# ESPAlarm.net
KiCad netlist of a schematic drawn in EAGLE
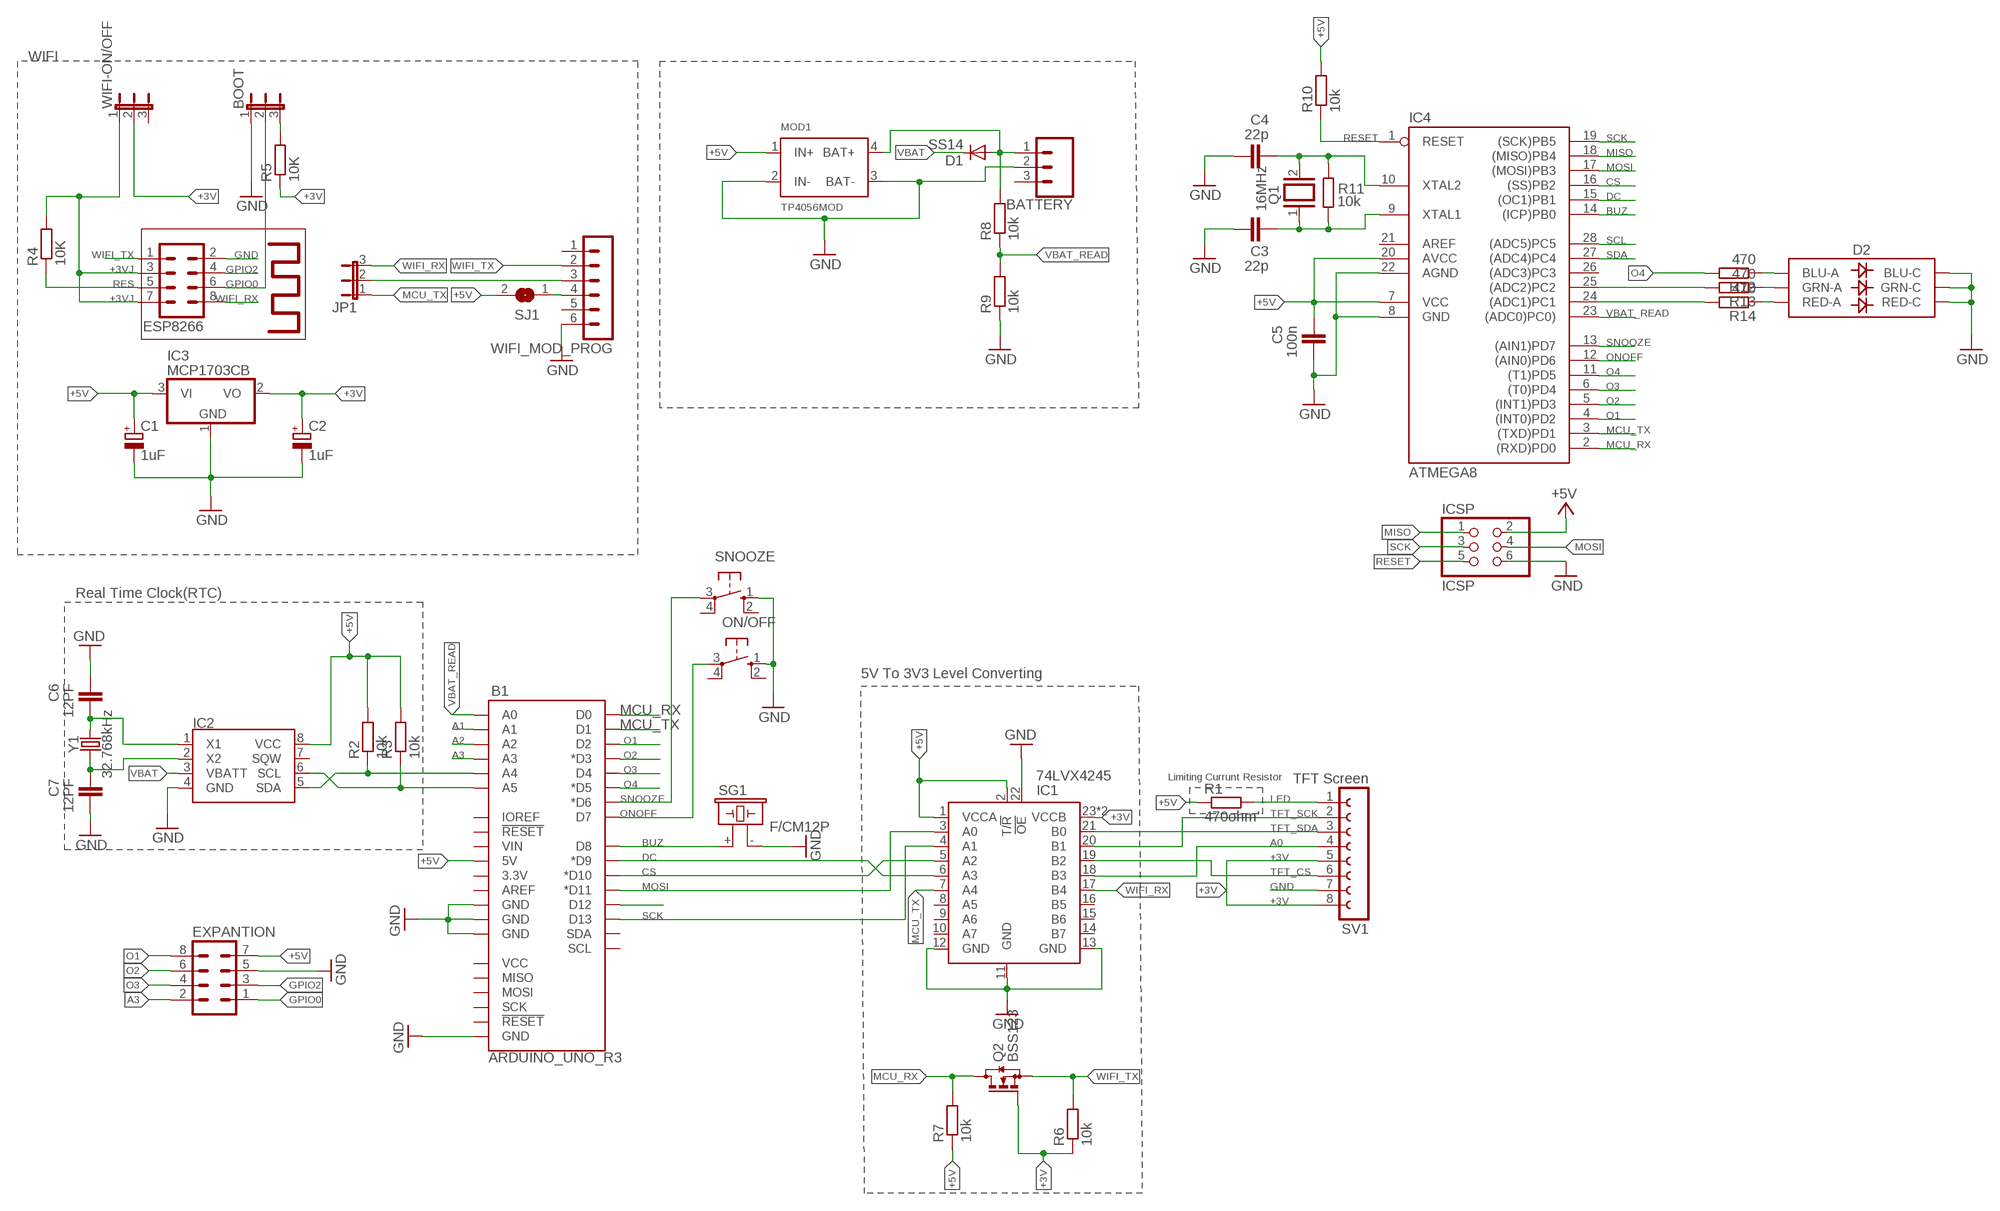
[diagram p0: schematic, sheet 1]

(export (version "E")
  (design (tool "Eeschema 10.0.6"))
  (components
    (comp (ref "B1")
      (value "ARDUINO_UNO_R3")
      (footprint "eagle-import:ARDUINO_R3")
      (libsource (lib "eagle-import") (part "ARDUINO_UNO_R3"))
    )
    (comp (ref "BATTERY")
      (value "CONN_03JST-PTH-VERT")
      (footprint "eagle-import:JST-3-PTH-VERT")
      (libsource (lib "eagle-import") (part "CONN_03JST-PTH-VERT"))
    )
    (comp (ref "BOOT")
      (value "JP2E")
      (footprint "eagle-import:JP2")
      (libsource (lib "eagle-import") (part "JP2E"))
    )
    (comp (ref "C1")
      (value "1uF")
      (footprint "eagle-import:E2,5-7")
      (libsource (lib "eagle-import") (part "CPOL-EUE2.5-7"))
    )
    (comp (ref "C2")
      (value "1uF")
      (footprint "eagle-import:E2,5-7")
      (libsource (lib "eagle-import") (part "CPOL-EUE2.5-7"))
    )
    (comp (ref "C3")
      (value "22p")
      (footprint "eagle-import:C0805")
      (libsource (lib "eagle-import") (part "C-EUC0805"))
    )
    (comp (ref "C4")
      (value "22p")
      (footprint "eagle-import:C0805")
      (libsource (lib "eagle-import") (part "C-EUC0805"))
    )
    (comp (ref "C5")
      (value "100n")
      (footprint "eagle-import:C0805")
      (libsource (lib "eagle-import") (part "C-EUC0805"))
    )
    (comp (ref "C6")
      (value "12PF")
      (footprint "eagle-import:C0805")
      (libsource (lib "eagle-import") (part "C-EUC0805"))
    )
    (comp (ref "C7")
      (value "12PF")
      (footprint "eagle-import:C0805")
      (libsource (lib "eagle-import") (part "C-EUC0805"))
    )
    (comp (ref "D1")
      (value "SS14")
      (footprint "eagle-import:DO214AC")
      (libsource (lib "eagle-import") (part "DIODE-DO214AC"))
    )
    (comp (ref "D2")
      (value "LED-RGBNO_IC")
      (footprint "eagle-import:LED-TRICOLOR-5050")
      (libsource (lib "eagle-import") (part "LED-RGBNO_IC"))
    )
    (comp (ref "ESP8266")
      (value "MA04-2")
      (footprint "eagle-import:MA04-2")
      (libsource (lib "eagle-import") (part "MA04-2"))
    )
    (comp (ref "EXPANTION")
      (value "MA04-2")
      (footprint "eagle-import:MA04-2")
      (libsource (lib "eagle-import") (part "MA04-2"))
    )
    (comp (ref "IC1")
      (value "74LVX4245")
      (footprint "eagle-import:TSSOP-24")
      (libsource (lib "eagle-import") (part "74LVX4245"))
    )
    (comp (ref "IC2")
      (value "DS1307")
      (footprint "eagle-import:DIP-08")
      (libsource (lib "eagle-import") (part "DS1307"))
    )
    (comp (ref "IC3")
      (value "MCP1703CB")
      (footprint "eagle-import:SOT23")
      (libsource (lib "eagle-import") (part "MCP1703CB"))
    )
    (comp (ref "IC4")
      (value "ATMEGA8")
      (footprint "eagle-import:DIL28-3")
      (libsource (lib "eagle-import") (part "AT90S4433P"))
    )
    (comp (ref "ICSP")
      (value "ICSP")
      (footprint "eagle-import:2X03")
      (libsource (lib "eagle-import") (part "PINHD-2X3"))
    )
    (comp (ref "JP1")
      (value "JP2E")
      (footprint "eagle-import:JP2")
      (libsource (lib "eagle-import") (part "JP2E"))
    )
    (comp (ref "MOD1")
      (value "TP4056MOD")
      (footprint "eagle-import:TP4056BRD")
      (libsource (lib "eagle-import") (part "TP4056MOD"))
    )
    (comp (ref "ON/OFF")
      (value "10-XX")
      (footprint "eagle-import:B3F-10XX")
      (fields (field (name "MPN") "B3F-1000"))
      (libsource (lib "eagle-import") (part "10-XX"))
    )
    (comp (ref "Q1")
      (value "16MHz")
      (footprint "eagle-import:SMARTPRJ_QS")
      (libsource (lib "eagle-import") (part "SMARTPRJ_XTAL/S"))
    )
    (comp (ref "Q2")
      (value "BSS123")
      (footprint "eagle-import:SOT23")
      (libsource (lib "eagle-import") (part "BSS123"))
    )
    (comp (ref "R1")
      (value "470ohm'")
      (footprint "eagle-import:M1206")
      (libsource (lib "eagle-import") (part "R-EU_M1206"))
    )
    (comp (ref "R2")
      (value "10k")
      (footprint "eagle-import:M1206")
      (libsource (lib "eagle-import") (part "R-EU_M1206"))
    )
    (comp (ref "R3")
      (value "10k")
      (footprint "eagle-import:M1206")
      (libsource (lib "eagle-import") (part "R-EU_M1206"))
    )
    (comp (ref "R4")
      (value "10K")
      (footprint "eagle-import:M1206")
      (libsource (lib "eagle-import") (part "R-EU_M1206"))
    )
    (comp (ref "R5")
      (value "10K")
      (footprint "eagle-import:M1206")
      (libsource (lib "eagle-import") (part "R-EU_M1206"))
    )
    (comp (ref "R6")
      (value "10k")
      (footprint "eagle-import:M1206")
      (libsource (lib "eagle-import") (part "R-EU_M1206"))
    )
    (comp (ref "R7")
      (value "10k")
      (footprint "eagle-import:M1206")
      (libsource (lib "eagle-import") (part "R-EU_M1206"))
    )
    (comp (ref "R8")
      (value "10k")
      (footprint "eagle-import:M1206")
      (libsource (lib "eagle-import") (part "R-EU_M1206"))
    )
    (comp (ref "R9")
      (value "10k")
      (footprint "eagle-import:M1206")
      (libsource (lib "eagle-import") (part "R-EU_M1206"))
    )
    (comp (ref "R10")
      (value "10k")
      (footprint "eagle-import:M1206")
      (libsource (lib "eagle-import") (part "R-EU_M1206"))
    )
    (comp (ref "R11")
      (value "10k")
      (footprint "eagle-import:M1206")
      (libsource (lib "eagle-import") (part "R-EU_M1206"))
    )
    (comp (ref "R12")
      (value "470")
      (footprint "eagle-import:M1206")
      (libsource (lib "eagle-import") (part "R-EU_M1206"))
    )
    (comp (ref "R13")
      (value "470")
      (footprint "eagle-import:M1206")
      (libsource (lib "eagle-import") (part "R-EU_M1206"))
    )
    (comp (ref "R14")
      (value "470")
      (footprint "eagle-import:M1206")
      (libsource (lib "eagle-import") (part "R-EU_M1206"))
    )
    (comp (ref "SG1")
      (value "F/CM12P")
      (footprint "eagle-import:F_CM12P")
      (libsource (lib "eagle-import") (part "F/CM12P"))
    )
    (comp (ref "SJ1") (value "SJ") (footprint "eagle-import:SJ") (libsource (lib "eagle-import") (part "SJ")))
    (comp (ref "SNOOZE")
      (value "10-XX")
      (footprint "eagle-import:B3F-10XX")
      (fields (field (name "MPN") "B3F-1000"))
      (libsource (lib "eagle-import") (part "10-XX"))
    )
    (comp (ref "SV1")
      (value "TFT Screen")
      (footprint "eagle-import:FE08")
      (libsource (lib "eagle-import") (part "FE08-1"))
    )
    (comp (ref "WIFI-ON/OFF")
      (value "JP2E")
      (footprint "eagle-import:JP2")
      (libsource (lib "eagle-import") (part "JP2E"))
    )
    (comp (ref "WIFI_MOD_PROG")
      (value "MA06-1")
      (footprint "eagle-import:MA06-1")
      (libsource (lib "eagle-import") (part "MA06-1"))
    )
    (comp (ref "Y1")
      (value "32.768kHz")
      (footprint "eagle-import:CRYSTAL-PTH-2X6-CYL")
      (libsource (lib "eagle-import") (part "CRYSTAL-32.768KHZPTH-2X6"))
    )
  )
  (nets
    (net (code "1") (name "+3V") (class "Default")
      (node (ref "C2") (pin "+") (pinfunction "+_+") (pintype "passive"))
      (node (ref "IC1") (pin "23") (pinfunction "VCCB_23") (pintype "power_in"))
      (node (ref "IC1") (pin "24") (pinfunction "VCCB_24") (pintype "power_in"))
      (node (ref "IC3") (pin "2") (pinfunction "VO_2") (pintype "passive"))
      (node (ref "Q2") (pin "1") (pinfunction "G_1") (pintype "passive"))
      (node (ref "R5") (pin "1") (pinfunction "1_1") (pintype "passive"))
      (node (ref "R6") (pin "1") (pinfunction "1_1") (pintype "passive"))
      (node (ref "SV1") (pin "5") (pinfunction "5_5") (pintype "passive"))
      (node (ref "SV1") (pin "8") (pinfunction "8_8") (pintype "passive"))
      (node (ref "WIFI-ON/OFF") (pin "2") (pinfunction "2_2") (pintype "passive"))
    )
    (net (code "2") (name "+5V") (class "Default")
      (node (ref "B1") (pin "5V") (pinfunction "5V_5V") (pintype "bidirectional"))
      (node (ref "C1") (pin "+") (pinfunction "+_+") (pintype "passive"))
      (node (ref "C5") (pin "2") (pinfunction "2_2") (pintype "passive"))
      (node (ref "EXPANTION") (pin "7") (pinfunction "7_7") (pintype "passive"))
      (node (ref "IC1") (pin "1") (pinfunction "VCCA_1") (pintype "power_in"))
      (node (ref "IC1") (pin "2") (pinfunction "T/~{R}_2") (pintype "open_collector"))
      (node (ref "IC2") (pin "8") (pinfunction "VCC_8") (pintype "bidirectional"))
      (node (ref "IC3") (pin "3") (pinfunction "VI_3") (pintype "input"))
      (node (ref "IC4") (pin "20") (pinfunction "AVCC_20") (pintype "power_in"))
      (node (ref "IC4") (pin "7") (pinfunction "VCC_7") (pintype "power_in"))
      (node (ref "ICSP") (pin "2") (pinfunction "2_2") (pintype "passive"))
      (node (ref "MOD1") (pin "1") (pinfunction "IN+_1") (pintype "bidirectional"))
      (node (ref "R1") (pin "1") (pinfunction "1_1") (pintype "passive"))
      (node (ref "R10") (pin "2") (pinfunction "2_2") (pintype "passive"))
      (node (ref "R2") (pin "2") (pinfunction "2_2") (pintype "passive"))
      (node (ref "R3") (pin "2") (pinfunction "2_2") (pintype "passive"))
      (node (ref "R7") (pin "1") (pinfunction "1_1") (pintype "passive"))
      (node (ref "SJ1") (pin "2") (pinfunction "2_2") (pintype "passive"))
    )
    (net (code "3") (name "/+3VJ") (class "Default")
      (node (ref "ESP8266") (pin "3") (pinfunction "3_3") (pintype "passive"))
      (node (ref "ESP8266") (pin "7") (pinfunction "7_7") (pintype "passive"))
      (node (ref "R4") (pin "2") (pinfunction "2_2") (pintype "passive"))
      (node (ref "WIFI-ON/OFF") (pin "1") (pinfunction "1_1") (pintype "passive"))
    )
    (net (code "4") (name "/A0") (class "Default")
      (node (ref "IC1") (pin "18") (pinfunction "B3_18") (pintype "bidirectional"))
      (node (ref "SV1") (pin "4") (pinfunction "4_4") (pintype "passive"))
    )
    (net (code "5") (name "/A1") (class "Default")
      (node (ref "B1") (pin "A1") (pinfunction "A1_A1") (pintype "bidirectional"))
      (node (ref "IC4") (pin "24") (pinfunction "(ADC1)PC1_24") (pintype "bidirectional"))
      (node (ref "R14") (pin "2") (pinfunction "2_2") (pintype "passive"))
    )
    (net (code "6") (name "/A2") (class "Default")
      (node (ref "B1") (pin "A2") (pinfunction "A2_A2") (pintype "bidirectional"))
      (node (ref "IC4") (pin "25") (pinfunction "(ADC2)PC2_25") (pintype "bidirectional"))
      (node (ref "R13") (pin "2") (pinfunction "2_2") (pintype "passive"))
    )
    (net (code "7") (name "/AREF") (class "Default")
      (node (ref "IC4") (pin "21") (pinfunction "AREF_21") (pintype "power_in"))
    )
    (net (code "8") (name "/BUZ") (class "Default")
      (node (ref "B1") (pin "D8") (pinfunction "D8_D8") (pintype "bidirectional"))
      (node (ref "IC4") (pin "14") (pinfunction "(ICP)PB0_14") (pintype "bidirectional"))
      (node (ref "SG1") (pin "+") (pinfunction "1_+") (pintype "passive"))
    )
    (net (code "9") (name "/CS") (class "Default")
      (node (ref "B1") (pin "D10") (pinfunction "*D10_D10") (pintype "bidirectional"))
      (node (ref "IC1") (pin "5") (pinfunction "A2_5") (pintype "bidirectional"))
      (node (ref "IC4") (pin "16") (pinfunction "(SS)PB2_16") (pintype "bidirectional"))
    )
    (net (code "10") (name "/DC") (class "Default")
      (node (ref "B1") (pin "D9") (pinfunction "*D9_D9") (pintype "bidirectional"))
      (node (ref "IC1") (pin "6") (pinfunction "A3_6") (pintype "bidirectional"))
      (node (ref "IC4") (pin "15") (pinfunction "(OC1)PB1_15") (pintype "bidirectional"))
    )
    (net (code "11") (name "/LED") (class "Default")
      (node (ref "R1") (pin "2") (pinfunction "2_2") (pintype "passive"))
      (node (ref "SV1") (pin "1") (pinfunction "1_1") (pintype "passive"))
    )
    (net (code "12") (name "/ONOFF") (class "Default")
      (node (ref "B1") (pin "D7") (pinfunction "D7_D7") (pintype "bidirectional"))
      (node (ref "IC4") (pin "12") (pinfunction "(AIN0)PD6_12") (pintype "bidirectional"))
      (node (ref "ON/OFF") (pin "3") (pinfunction "P_3") (pintype "passive"))
    )
    (net (code "13") (name "/RES") (class "Default")
      (node (ref "ESP8266") (pin "5") (pinfunction "5_5") (pintype "passive"))
      (node (ref "R4") (pin "1") (pinfunction "1_1") (pintype "passive"))
    )
    (net (code "14") (name "/SCL") (class "Default")
      (node (ref "B1") (pin "A5") (pinfunction "A5_A5") (pintype "bidirectional"))
      (node (ref "IC2") (pin "6") (pinfunction "SCL_6") (pintype "bidirectional"))
      (node (ref "IC4") (pin "28") (pinfunction "(ADC5)PC5_28") (pintype "bidirectional"))
      (node (ref "R3") (pin "1") (pinfunction "1_1") (pintype "passive"))
    )
    (net (code "15") (name "/SDA") (class "Default")
      (node (ref "B1") (pin "A4") (pinfunction "A4_A4") (pintype "bidirectional"))
      (node (ref "IC2") (pin "5") (pinfunction "SDA_5") (pintype "bidirectional"))
      (node (ref "IC4") (pin "27") (pinfunction "(ADC4)PC4_27") (pintype "bidirectional"))
      (node (ref "R2") (pin "1") (pinfunction "1_1") (pintype "passive"))
    )
    (net (code "16") (name "/SNOOZE") (class "Default")
      (node (ref "B1") (pin "D6") (pinfunction "*D6_D6") (pintype "bidirectional"))
      (node (ref "IC4") (pin "13") (pinfunction "(AIN1)PD7_13") (pintype "bidirectional"))
      (node (ref "SNOOZE") (pin "3") (pinfunction "P_3") (pintype "passive"))
    )
    (net (code "17") (name "/TFT_CS") (class "Default")
      (node (ref "IC1") (pin "19") (pinfunction "B2_19") (pintype "bidirectional"))
      (node (ref "SV1") (pin "6") (pinfunction "6_6") (pintype "passive"))
    )
    (net (code "18") (name "/TFT_SCK") (class "Default")
      (node (ref "IC1") (pin "20") (pinfunction "B1_20") (pintype "bidirectional"))
      (node (ref "SV1") (pin "2") (pinfunction "2_2") (pintype "passive"))
    )
    (net (code "19") (name "/TFT_SDA") (class "Default")
      (node (ref "IC1") (pin "21") (pinfunction "B0_21") (pintype "bidirectional"))
      (node (ref "SV1") (pin "3") (pinfunction "3_3") (pintype "passive"))
    )
    (net (code "20") (name "A3") (class "Default")
      (node (ref "B1") (pin "A3") (pinfunction "A3_A3") (pintype "bidirectional"))
      (node (ref "EXPANTION") (pin "2") (pinfunction "2_2") (pintype "passive"))
    )
    (net (code "21") (name "GND") (class "Default")
      (node (ref "B1") (pin "GND@1") (pinfunction "GND_GND@1") (pintype "bidirectional"))
      (node (ref "B1") (pin "GND@2") (pinfunction "GND_GND@2") (pintype "bidirectional"))
      (node (ref "B1") (pin "GND@3") (pinfunction "GND_GND@3") (pintype "bidirectional"))
      (node (ref "B1") (pin "GND@4") (pinfunction "GND_GND@4") (pintype "bidirectional"))
      (node (ref "BATTERY") (pin "2") (pinfunction "2_2") (pintype "passive"))
      (node (ref "BOOT") (pin "1") (pinfunction "1_1") (pintype "passive"))
      (node (ref "C1") (pin "-") (pinfunction "-_-") (pintype "passive"))
      (node (ref "C2") (pin "-") (pinfunction "-_-") (pintype "passive"))
      (node (ref "C3") (pin "1") (pinfunction "1_1") (pintype "passive"))
      (node (ref "C4") (pin "1") (pinfunction "1_1") (pintype "passive"))
      (node (ref "C5") (pin "1") (pinfunction "1_1") (pintype "passive"))
      (node (ref "C6") (pin "2") (pinfunction "2_2") (pintype "passive"))
      (node (ref "C7") (pin "1") (pinfunction "1_1") (pintype "passive"))
      (node (ref "D2") (pin "4") (pinfunction "BLU-C_4") (pintype "bidirectional"))
      (node (ref "D2") (pin "5") (pinfunction "RED-C_5") (pintype "bidirectional"))
      (node (ref "D2") (pin "6") (pinfunction "GRN-C_6") (pintype "bidirectional"))
      (node (ref "ESP8266") (pin "2") (pinfunction "2_2") (pintype "passive"))
      (node (ref "EXPANTION") (pin "5") (pinfunction "5_5") (pintype "passive"))
      (node (ref "IC1") (pin "11") (pinfunction "GND_11") (pintype "power_in"))
      (node (ref "IC1") (pin "12") (pinfunction "GND_12") (pintype "power_in"))
      (node (ref "IC1") (pin "13") (pinfunction "GND_13") (pintype "power_in"))
      (node (ref "IC1") (pin "22") (pinfunction "~{OE}_22") (pintype "open_collector"))
      (node (ref "IC2") (pin "4") (pinfunction "GND_4") (pintype "bidirectional"))
      (node (ref "IC3") (pin "1") (pinfunction "GND_1") (pintype "passive"))
      (node (ref "IC4") (pin "22") (pinfunction "AGND_22") (pintype "power_in"))
      (node (ref "IC4") (pin "8") (pinfunction "GND_8") (pintype "power_in"))
      (node (ref "ICSP") (pin "6") (pinfunction "6_6") (pintype "passive"))
      (node (ref "MOD1") (pin "2") (pinfunction "IN-_2") (pintype "bidirectional"))
      (node (ref "MOD1") (pin "3") (pinfunction "BAT-_3") (pintype "bidirectional"))
      (node (ref "ON/OFF") (pin "1") (pinfunction "S_1") (pintype "passive"))
      (node (ref "R9") (pin "1") (pinfunction "1_1") (pintype "passive"))
      (node (ref "SG1") (pin "-") (pinfunction "2_-") (pintype "passive"))
      (node (ref "SNOOZE") (pin "1") (pinfunction "S_1") (pintype "passive"))
      (node (ref "SV1") (pin "7") (pinfunction "7_7") (pintype "passive"))
      (node (ref "WIFI_MOD_PROG") (pin "6") (pinfunction "6_6") (pintype "passive"))
    )
    (net (code "22") (name "GPIO0") (class "Default")
      (node (ref "BOOT") (pin "2") (pinfunction "2_2") (pintype "passive"))
      (node (ref "ESP8266") (pin "6") (pinfunction "6_6") (pintype "passive"))
      (node (ref "EXPANTION") (pin "1") (pinfunction "1_1") (pintype "passive"))
    )
    (net (code "23") (name "GPIO2") (class "Default")
      (node (ref "ESP8266") (pin "4") (pinfunction "4_4") (pintype "passive"))
      (node (ref "EXPANTION") (pin "3") (pinfunction "3_3") (pintype "passive"))
    )
    (net (code "24") (name "MCU_RX") (class "Default")
      (node (ref "B1") (pin "D0") (pinfunction "D0_D0") (pintype "bidirectional"))
      (node (ref "IC4") (pin "2") (pinfunction "(RXD)PD0_2") (pintype "bidirectional"))
      (node (ref "Q2") (pin "3") (pinfunction "D_3") (pintype "passive"))
      (node (ref "R7") (pin "2") (pinfunction "2_2") (pintype "passive"))
    )
    (net (code "25") (name "MCU_TX") (class "Default")
      (node (ref "B1") (pin "D1") (pinfunction "D1_D1") (pintype "bidirectional"))
      (node (ref "IC1") (pin "7") (pinfunction "A4_7") (pintype "bidirectional"))
      (node (ref "IC4") (pin "3") (pinfunction "(TXD)PD1_3") (pintype "bidirectional"))
      (node (ref "JP1") (pin "1") (pinfunction "1_1") (pintype "passive"))
    )
    (net (code "26") (name "MISO") (class "Default")
      (node (ref "IC4") (pin "18") (pinfunction "(MISO)PB4_18") (pintype "bidirectional"))
      (node (ref "ICSP") (pin "1") (pinfunction "1_1") (pintype "passive"))
    )
    (net (code "27") (name "MOSI") (class "Default")
      (node (ref "B1") (pin "D11") (pinfunction "*D11_D11") (pintype "bidirectional"))
      (node (ref "IC1") (pin "3") (pinfunction "A0_3") (pintype "bidirectional"))
      (node (ref "IC4") (pin "17") (pinfunction "(MOSI)PB3_17") (pintype "bidirectional"))
      (node (ref "ICSP") (pin "4") (pinfunction "4_4") (pintype "passive"))
    )
    (net (code "28") (name "Net-(BOOT-Pad3)") (class "Default")
      (node (ref "BOOT") (pin "3") (pinfunction "3_3") (pintype "passive"))
      (node (ref "R5") (pin "2") (pinfunction "2_2") (pintype "passive"))
    )
    (net (code "29") (name "Net-(D2-BLU-A)") (class "Default")
      (node (ref "D2") (pin "3") (pinfunction "BLU-A_3") (pintype "bidirectional"))
      (node (ref "R12") (pin "1") (pinfunction "1_1") (pintype "passive"))
    )
    (net (code "30") (name "Net-(D2-GRN-A)") (class "Default")
      (node (ref "D2") (pin "1") (pinfunction "GRN-A_1") (pintype "bidirectional"))
      (node (ref "R13") (pin "1") (pinfunction "1_1") (pintype "passive"))
    )
    (net (code "31") (name "Net-(D2-RED-A)") (class "Default")
      (node (ref "D2") (pin "2") (pinfunction "RED-A_2") (pintype "bidirectional"))
      (node (ref "R14") (pin "1") (pinfunction "1_1") (pintype "passive"))
    )
    (net (code "32") (name "Net-(IC2-X1)") (class "Default")
      (node (ref "C6") (pin "1") (pinfunction "1_1") (pintype "passive"))
      (node (ref "IC2") (pin "1") (pinfunction "X1_1") (pintype "bidirectional"))
      (node (ref "Y1") (pin "2") (pinfunction "2_2") (pintype "passive"))
    )
    (net (code "33") (name "Net-(IC2-X2)") (class "Default")
      (node (ref "C7") (pin "2") (pinfunction "2_2") (pintype "passive"))
      (node (ref "IC2") (pin "2") (pinfunction "X2_2") (pintype "bidirectional"))
      (node (ref "Y1") (pin "1") (pinfunction "1_1") (pintype "passive"))
    )
    (net (code "34") (name "Net-(IC4-XTAL1)") (class "Default")
      (node (ref "C3") (pin "2") (pinfunction "2_2") (pintype "passive"))
      (node (ref "IC4") (pin "9") (pinfunction "XTAL1_9") (pintype "bidirectional"))
      (node (ref "Q1") (pin "1") (pinfunction "1_1") (pintype "passive"))
      (node (ref "R11") (pin "1") (pinfunction "1_1") (pintype "passive"))
    )
    (net (code "35") (name "Net-(IC4-XTAL2)") (class "Default")
      (node (ref "C4") (pin "2") (pinfunction "2_2") (pintype "passive"))
      (node (ref "IC4") (pin "10") (pinfunction "XTAL2_10") (pintype "bidirectional"))
      (node (ref "Q1") (pin "2") (pinfunction "2_2") (pintype "passive"))
      (node (ref "R11") (pin "2") (pinfunction "2_2") (pintype "passive"))
    )
    (net (code "36") (name "Net-(JP1-Pad2)") (class "Default")
      (node (ref "JP1") (pin "2") (pinfunction "2_2") (pintype "passive"))
      (node (ref "WIFI_MOD_PROG") (pin "3") (pinfunction "3_3") (pintype "passive"))
    )
    (net (code "37") (name "Net-(MOD1-BAT+)") (class "Default")
      (node (ref "BATTERY") (pin "1") (pinfunction "1_1") (pintype "passive"))
      (node (ref "D1") (pin "A") (pinfunction "A_A") (pintype "passive"))
      (node (ref "MOD1") (pin "4") (pinfunction "BAT+_4") (pintype "bidirectional"))
      (node (ref "R8") (pin "2") (pinfunction "2_2") (pintype "passive"))
    )
    (net (code "38") (name "Net-(SJ1-Pad1)") (class "Default")
      (node (ref "SJ1") (pin "1") (pinfunction "1_1") (pintype "passive"))
      (node (ref "WIFI_MOD_PROG") (pin "4") (pinfunction "4_4") (pintype "passive"))
    )
    (net (code "39") (name "O1") (class "Default")
      (node (ref "B1") (pin "D2") (pinfunction "D2_D2") (pintype "bidirectional"))
      (node (ref "EXPANTION") (pin "8") (pinfunction "8_8") (pintype "passive"))
      (node (ref "IC4") (pin "4") (pinfunction "(INT0)PD2_4") (pintype "bidirectional"))
    )
    (net (code "40") (name "O2") (class "Default")
      (node (ref "B1") (pin "D3") (pinfunction "*D3_D3") (pintype "bidirectional"))
      (node (ref "EXPANTION") (pin "6") (pinfunction "6_6") (pintype "passive"))
      (node (ref "IC4") (pin "5") (pinfunction "(INT1)PD3_5") (pintype "bidirectional"))
    )
    (net (code "41") (name "O3") (class "Default")
      (node (ref "B1") (pin "D4") (pinfunction "D4_D4") (pintype "bidirectional"))
      (node (ref "EXPANTION") (pin "4") (pinfunction "4_4") (pintype "passive"))
      (node (ref "IC4") (pin "6") (pinfunction "(T0)PD4_6") (pintype "bidirectional"))
    )
    (net (code "42") (name "O4") (class "Default")
      (node (ref "B1") (pin "D5") (pinfunction "*D5_D5") (pintype "bidirectional"))
      (node (ref "IC4") (pin "11") (pinfunction "(T1)PD5_11") (pintype "bidirectional"))
      (node (ref "R12") (pin "2") (pinfunction "2_2") (pintype "passive"))
    )
    (net (code "43") (name "RESET") (class "Default")
      (node (ref "IC4") (pin "1") (pinfunction "RESET_1") (pintype "input"))
      (node (ref "ICSP") (pin "5") (pinfunction "5_5") (pintype "passive"))
      (node (ref "R10") (pin "1") (pinfunction "1_1") (pintype "passive"))
    )
    (net (code "44") (name "SCK") (class "Default")
      (node (ref "B1") (pin "D13") (pinfunction "D13_D13") (pintype "bidirectional"))
      (node (ref "IC1") (pin "4") (pinfunction "A1_4") (pintype "bidirectional"))
      (node (ref "IC4") (pin "19") (pinfunction "(SCK)PB5_19") (pintype "bidirectional"))
      (node (ref "ICSP") (pin "3") (pinfunction "3_3") (pintype "passive"))
    )
    (net (code "45") (name "VBAT") (class "Default")
      (node (ref "D1") (pin "C") (pinfunction "C_C") (pintype "passive"))
      (node (ref "IC2") (pin "3") (pinfunction "VBATT_3") (pintype "bidirectional"))
    )
    (net (code "46") (name "VBAT_READ") (class "Default")
      (node (ref "B1") (pin "A0") (pinfunction "A0_A0") (pintype "bidirectional"))
      (node (ref "IC4") (pin "23") (pinfunction "(ADC0)PC0)_23") (pintype "bidirectional"))
      (node (ref "R8") (pin "1") (pinfunction "1_1") (pintype "passive"))
      (node (ref "R9") (pin "2") (pinfunction "2_2") (pintype "passive"))
    )
    (net (code "47") (name "WIFI_RX") (class "Default")
      (node (ref "ESP8266") (pin "8") (pinfunction "8_8") (pintype "passive"))
      (node (ref "IC1") (pin "17") (pinfunction "B4_17") (pintype "bidirectional"))
      (node (ref "JP1") (pin "3") (pinfunction "3_3") (pintype "passive"))
    )
    (net (code "48") (name "WIFI_TX") (class "Default")
      (node (ref "ESP8266") (pin "1") (pinfunction "1_1") (pintype "passive"))
      (node (ref "Q2") (pin "2") (pinfunction "S_2") (pintype "passive"))
      (node (ref "R6") (pin "2") (pinfunction "2_2") (pintype "passive"))
      (node (ref "WIFI_MOD_PROG") (pin "2") (pinfunction "2_2") (pintype "passive"))
    )
    (net (code "49") (name "unconnected-(B1-Pad3.3V)") (class "Default")
      (node (ref "B1") (pin "3.3V") (pinfunction "3.3V_3.3V") (pintype "bidirectional"))
    )
    (net (code "50") (name "unconnected-(B1-PadAREF)") (class "Default")
      (node (ref "B1") (pin "AREF") (pinfunction "AREF_AREF") (pintype "bidirectional"))
    )
    (net (code "51") (name "unconnected-(B1-PadD12)") (class "Default")
      (node (ref "B1") (pin "D12") (pinfunction "D12_D12") (pintype "bidirectional"))
    )
    (net (code "52") (name "unconnected-(B1-PadIOREF)") (class "Default")
      (node (ref "B1") (pin "IOREF") (pinfunction "IOREF_IOREF") (pintype "bidirectional"))
    )
    (net (code "53") (name "unconnected-(B1-PadMISO)") (class "Default")
      (node (ref "B1") (pin "MISO") (pinfunction "MISO_MISO") (pintype "bidirectional"))
    )
    (net (code "54") (name "unconnected-(B1-PadMOSI)") (class "Default")
      (node (ref "B1") (pin "MOSI") (pinfunction "MOSI_MOSI") (pintype "bidirectional"))
    )
    (net (code "55") (name "unconnected-(B1-PadSCK)") (class "Default")
      (node (ref "B1") (pin "SCK") (pinfunction "SCK_SCK") (pintype "bidirectional"))
    )
    (net (code "56") (name "unconnected-(B1-PadSCL)") (class "Default")
      (node (ref "B1") (pin "SCL") (pinfunction "SCL_SCL") (pintype "bidirectional"))
    )
    (net (code "57") (name "unconnected-(B1-PadSDA)") (class "Default")
      (node (ref "B1") (pin "SDA") (pinfunction "SDA_SDA") (pintype "bidirectional"))
    )
    (net (code "58") (name "unconnected-(B1-PadVCC)") (class "Default")
      (node (ref "B1") (pin "VCC") (pinfunction "VCC_VCC") (pintype "bidirectional"))
    )
    (net (code "59") (name "unconnected-(B1-PadVIN)") (class "Default")
      (node (ref "B1") (pin "VIN") (pinfunction "VIN_VIN") (pintype "bidirectional"))
    )
    (net (code "60") (name "unconnected-(B1-~{RESET}-PadRESET@1)") (class "Default")
      (node (ref "B1") (pin "RESET@1") (pinfunction "~{RESET}_RESET@1") (pintype "bidirectional"))
    )
    (net (code "61") (name "unconnected-(B1-~{RESET}-PadRESET@2)") (class "Default")
      (node (ref "B1") (pin "RESET@2") (pinfunction "~{RESET}_RESET@2") (pintype "bidirectional"))
    )
    (net (code "62") (name "unconnected-(BATTERY-Pad3)") (class "Default")
      (node (ref "BATTERY") (pin "3") (pinfunction "3_3") (pintype "passive"))
    )
    (net (code "63") (name "unconnected-(IC1-A5-Pad8)") (class "Default")
      (node (ref "IC1") (pin "8") (pinfunction "A5_8") (pintype "bidirectional"))
    )
    (net (code "64") (name "unconnected-(IC1-A6-Pad9)") (class "Default")
      (node (ref "IC1") (pin "9") (pinfunction "A6_9") (pintype "bidirectional"))
    )
    (net (code "65") (name "unconnected-(IC1-A7-Pad10)") (class "Default")
      (node (ref "IC1") (pin "10") (pinfunction "A7_10") (pintype "bidirectional"))
    )
    (net (code "66") (name "unconnected-(IC1-B5-Pad16)") (class "Default")
      (node (ref "IC1") (pin "16") (pinfunction "B5_16") (pintype "bidirectional"))
    )
    (net (code "67") (name "unconnected-(IC1-B6-Pad15)") (class "Default")
      (node (ref "IC1") (pin "15") (pinfunction "B6_15") (pintype "bidirectional"))
    )
    (net (code "68") (name "unconnected-(IC1-B7-Pad14)") (class "Default")
      (node (ref "IC1") (pin "14") (pinfunction "B7_14") (pintype "bidirectional"))
    )
    (net (code "69") (name "unconnected-(IC2-SQW-Pad7)") (class "Default")
      (node (ref "IC2") (pin "7") (pinfunction "SQW_7") (pintype "bidirectional"))
    )
    (net (code "70") (name "unconnected-(IC4-(ADC3)PC3-Pad26)") (class "Default")
      (node (ref "IC4") (pin "26") (pinfunction "(ADC3)PC3_26") (pintype "bidirectional"))
    )
    (net (code "71") (name "unconnected-(ON/OFF-P1-Pad4)") (class "Default")
      (node (ref "ON/OFF") (pin "4") (pinfunction "P1_4") (pintype "passive"))
    )
    (net (code "72") (name "unconnected-(ON/OFF-S1-Pad2)") (class "Default")
      (node (ref "ON/OFF") (pin "2") (pinfunction "S1_2") (pintype "passive"))
    )
    (net (code "73") (name "unconnected-(SNOOZE-P1-Pad4)") (class "Default")
      (node (ref "SNOOZE") (pin "4") (pinfunction "P1_4") (pintype "passive"))
    )
    (net (code "74") (name "unconnected-(SNOOZE-S1-Pad2)") (class "Default")
      (node (ref "SNOOZE") (pin "2") (pinfunction "S1_2") (pintype "passive"))
    )
    (net (code "75") (name "unconnected-(WIFI-ON/OFF-Pad3)") (class "Default")
      (node (ref "WIFI-ON/OFF") (pin "3") (pinfunction "3_3") (pintype "passive"))
    )
    (net (code "76") (name "unconnected-(WIFI_MOD_PROG-Pad1)") (class "Default")
      (node (ref "WIFI_MOD_PROG") (pin "1") (pinfunction "1_1") (pintype "passive"))
    )
    (net (code "77") (name "unconnected-(WIFI_MOD_PROG-Pad5)") (class "Default")
      (node (ref "WIFI_MOD_PROG") (pin "5") (pinfunction "5_5") (pintype "passive"))
    )
  )
)
